# Power_Connectors.net
KiCad netlist of a schematic drawn in Altium Designer
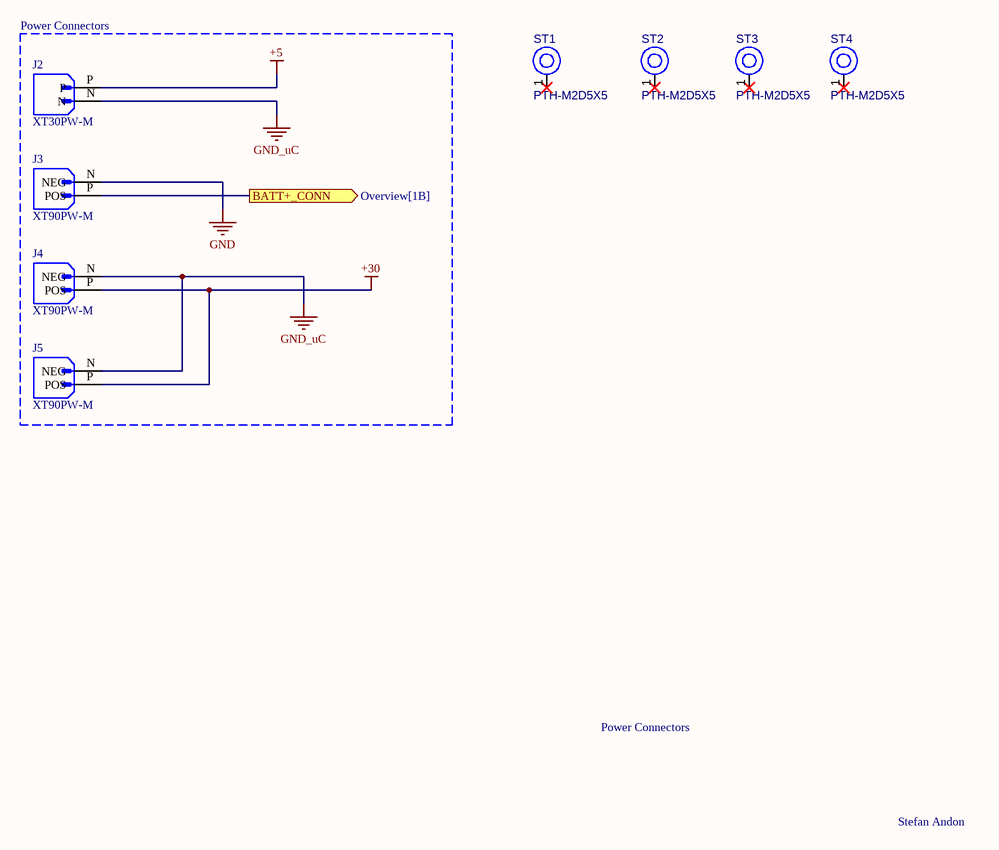
[diagram p0: Power_Connectors.SchDoc]

(export (version "E")
  (design (tool "Eeschema 10.0.6"))
  (components
    (comp (ref "J2")
      (value "XT30PW-M")
      (footprint "AMASS_XT30PW-M")
      (description "Socket; DC supply; XT30; male; PIN: 2; on PCBs; THT; Colour: yellow")
      (fields (field (name "MF") "AMASS"))
      (libsource (lib "Stefan Andon") (part "XT30PW-M"))
    )
    (comp (ref "J3")
      (value "XT90PW-M")
      (footprint "AMASS_XT90PW-M")
      (description "Socket; DC supply; XT90; male; PIN: 2; on PCBs; THT; Colour: yellow")
      (fields (field (name "MF") "AMASS"))
      (libsource (lib "Stefan Andon") (part "XT90PW-M"))
    )
    (comp (ref "J4")
      (value "XT90PW-M")
      (footprint "AMASS_XT90PW-M")
      (description "Socket; DC supply; XT90; male; PIN: 2; on PCBs; THT; Colour: yellow")
      (fields (field (name "MF") "AMASS"))
      (libsource (lib "Stefan Andon") (part "XT90PW-M"))
    )
    (comp (ref "J5")
      (value "XT90PW-M")
      (footprint "AMASS_XT90PW-M")
      (description "Socket; DC supply; XT90; male; PIN: 2; on PCBs; THT; Colour: yellow")
      (fields (field (name "MF") "AMASS"))
      (libsource (lib "Stefan Andon") (part "XT90PW-M"))
    )
    (comp (ref "ST1")
      (value "PTH-M2D5X5")
      (footprint "PTH-M2D5X5")
      (description "M2 PTH (2.5mm), 5mm pad")
      (libsource (lib "Stefan Andon") (part "CMP-00028-00000-1"))
    )
    (comp (ref "ST2")
      (value "PTH-M2D5X5")
      (footprint "PTH-M2D5X5")
      (description "M2 PTH (2.5mm), 5mm pad")
      (libsource (lib "Stefan Andon") (part "CMP-00028-00000-1"))
    )
    (comp (ref "ST3")
      (value "PTH-M2D5X5")
      (footprint "PTH-M2D5X5")
      (description "M2 PTH (2.5mm), 5mm pad")
      (libsource (lib "Stefan Andon") (part "CMP-00028-00000-1"))
    )
    (comp (ref "ST4")
      (value "PTH-M2D5X5")
      (footprint "PTH-M2D5X5")
      (description "M2 PTH (2.5mm), 5mm pad")
      (libsource (lib "Stefan Andon") (part "CMP-00028-00000-1"))
    )
  )
  (nets
    (net (code "1") (name "+5") (class "Default")
      (node (ref "J2") (pin "P") (pinfunction "P_P") (pintype "power_in"))
    )
    (net (code "2") (name "+30") (class "Default")
      (node (ref "J4") (pin "P") (pinfunction "POS_P") (pintype "passive"))
      (node (ref "J5") (pin "P") (pinfunction "POS_P") (pintype "passive"))
    )
    (net (code "3") (name "/BATT+_CONN") (class "Default")
      (node (ref "J3") (pin "P") (pinfunction "POS_P") (pintype "passive"))
    )
    (net (code "4") (name "GND") (class "Default")
      (node (ref "J3") (pin "N") (pinfunction "NEG_N") (pintype "passive"))
    )
    (net (code "5") (name "GND_uC") (class "Default")
      (node (ref "J2") (pin "N") (pinfunction "N_N") (pintype "power_in"))
      (node (ref "J4") (pin "N") (pinfunction "NEG_N") (pintype "passive"))
      (node (ref "J5") (pin "N") (pinfunction "NEG_N") (pintype "passive"))
    )
    (net (code "6") (name "unconnected-(ST1-H1-Pad1)") (class "Default")
      (node (ref "ST1") (pin "1") (pinfunction "H1_1") (pintype "passive+no_connect"))
    )
    (net (code "7") (name "unconnected-(ST2-H1-Pad1)") (class "Default")
      (node (ref "ST2") (pin "1") (pinfunction "H1_1") (pintype "passive+no_connect"))
    )
    (net (code "8") (name "unconnected-(ST3-H1-Pad1)") (class "Default")
      (node (ref "ST3") (pin "1") (pinfunction "H1_1") (pintype "passive+no_connect"))
    )
    (net (code "9") (name "unconnected-(ST4-H1-Pad1)") (class "Default")
      (node (ref "ST4") (pin "1") (pinfunction "H1_1") (pintype "passive+no_connect"))
    )
  )
)
